# Analog.net
KiCad netlist of a schematic drawn in Altium Designer
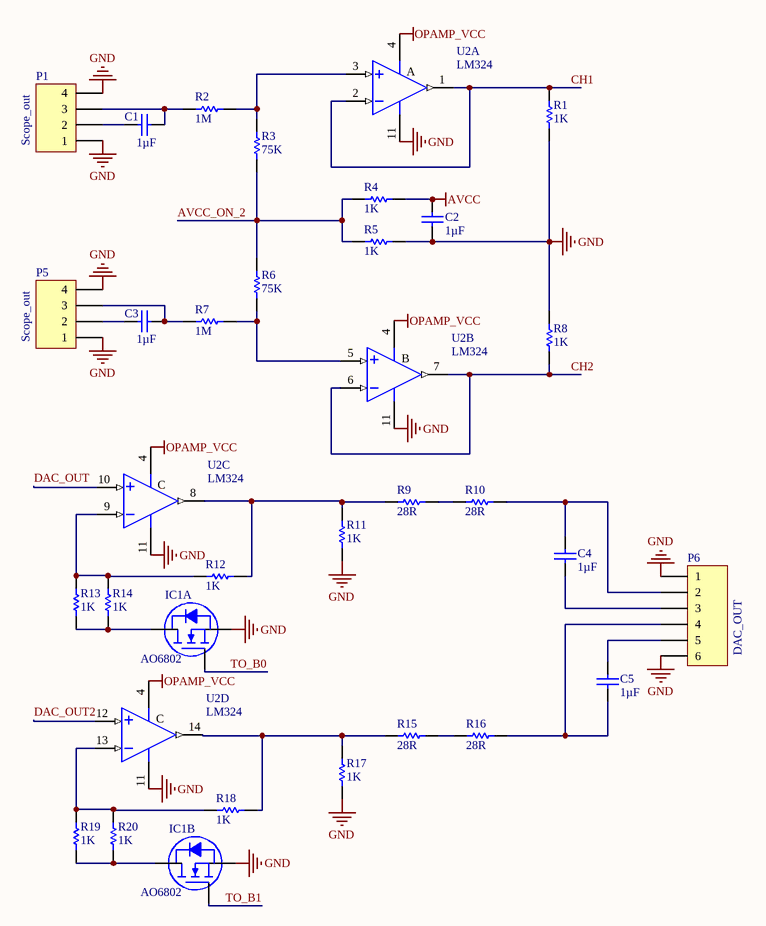
[diagram p0: Analog.SchDoc]

(export (version "E")
  (design (tool "Eeschema 10.0.6"))
  (components
    (comp (ref "C1")
      (value "1µF")
      (footprint "CAPC200X125X75L45N")
      (description "1µF 25V Ceramic Capacitor X5R 0805 (2012 Metric) 0.079\" L x 0.049\" W (2.00mm x 1.25mm)")
      (fields
        (field (name "MANUFACTURER") "Wurth Electronics")
        (field (name "MANUFACTURER PART NUMBER") "885012107015")
      )
      (libsource (lib "labrador") (part "885012107015"))
    )
    (comp (ref "C2")
      (value "1µF")
      (footprint "CAPC200X125X75L45N")
      (description "1µF 25V Ceramic Capacitor X5R 0805 (2012 Metric) 0.079\" L x 0.049\" W (2.00mm x 1.25mm)")
      (fields
        (field (name "MANUFACTURER") "Wurth Electronics")
        (field (name "MANUFACTURER PART NUMBER") "885012107015")
      )
      (libsource (lib "labrador") (part "885012107015"))
    )
    (comp (ref "C3")
      (value "1µF")
      (footprint "CAPC200X125X75L45N")
      (description "1µF 25V Ceramic Capacitor X5R 0805 (2012 Metric) 0.079\" L x 0.049\" W (2.00mm x 1.25mm)")
      (fields
        (field (name "MANUFACTURER") "Wurth Electronics")
        (field (name "MANUFACTURER PART NUMBER") "885012107015")
      )
      (libsource (lib "labrador") (part "885012107015"))
    )
    (comp (ref "C4")
      (value "1µF")
      (footprint "CAPC200X125X75L45N")
      (description "1µF 25V Ceramic Capacitor X5R 0805 (2012 Metric) 0.079\" L x 0.049\" W (2.00mm x 1.25mm)")
      (fields
        (field (name "MANUFACTURER") "Wurth Electronics")
        (field (name "MANUFACTURER PART NUMBER") "885012107015")
      )
      (libsource (lib "labrador") (part "885012107015"))
    )
    (comp (ref "C5")
      (value "1µF")
      (footprint "CAPC200X125X75L45N")
      (description "1µF 25V Ceramic Capacitor X5R 0805 (2012 Metric) 0.079\" L x 0.049\" W (2.00mm x 1.25mm)")
      (fields
        (field (name "MANUFACTURER") "Wurth Electronics")
        (field (name "MANUFACTURER PART NUMBER") "885012107015")
      )
      (libsource (lib "labrador") (part "885012107015"))
    )
    (comp (ref "IC1")
      (value "AO6802")
      (footprint "ALPHAOMEGA TSOP-6")
      (description "MOSFET 2N-CH 30V 3.5A 6-TSOP")
      (fields (field (name "MANUFACTURER") "Alpha & Omega"))
      (libsource (lib "labrador") (part "ALPHAOMEGA TSOP-6"))
    )
    (comp (ref "P1")
      (value "Scope_out")
      (footprint "HDR1X4")
      (description "Header, 4-Pin")
      (fields (field (name "PUBLISHER") "Altium Limited"))
      (libsource (lib "labrador") (part "Header 4"))
    )
    (comp (ref "P5")
      (value "Scope_out")
      (footprint "HDR1X4")
      (description "Header, 4-Pin")
      (fields (field (name "PUBLISHER") "Altium Limited"))
      (libsource (lib "labrador") (part "Header 4"))
    )
    (comp (ref "P6")
      (value "DAC_OUT")
      (footprint "HDR1X6")
      (description "Header, 6-Pin")
      (fields (field (name "PUBLISHER") "Altium Limited"))
      (libsource (lib "labrador") (part "Header 6"))
    )
    (comp (ref "R1")
      (value "1K")
      (footprint "RESC200X125X50L35N")
      (description "RES SMD 1K OHM 1% 1/8W 0805")
      (fields
        (field (name "MANUFACTURER") "Yageo")
        (field (name "MANUFACTURER PART NUMBER") "RC0805FR-071KL")
      )
      (libsource (lib "labrador") (part "RC0805FR-071KL"))
    )
    (comp (ref "R2")
      (value "1M")
      (footprint "RESC200X125X50L35N")
      (description "RES SMD 1M OHM 5% 1/8W 0805")
      (fields
        (field (name "MANUFACTURER") "Yageo")
        (field (name "MANUFACTURER PART NUMBER") "RC0805JR-071ML")
      )
      (libsource (lib "labrador") (part "RC0805JR-071ML"))
    )
    (comp (ref "R3")
      (value "75K")
      (footprint "RESC200X125X50L35N")
      (description "RES SMD 75K OHM 1% 1/8W 0805")
      (fields
        (field (name "MANUFACTURER") "Yageo")
        (field (name "MANUFACTURER PART NUMBER") "RT0805FRE0775KL")
      )
      (libsource (lib "labrador") (part "RT0805FRE0775KL"))
    )
    (comp (ref "R4")
      (value "1K")
      (footprint "RESC200X125X50L35N")
      (description "RES SMD 1K OHM 1% 1/8W 0805")
      (fields
        (field (name "MANUFACTURER") "Yageo")
        (field (name "MANUFACTURER PART NUMBER") "RC0805FR-071KL")
      )
      (libsource (lib "labrador") (part "RC0805FR-071KL"))
    )
    (comp (ref "R5")
      (value "1K")
      (footprint "RESC200X125X50L35N")
      (description "RES SMD 1K OHM 1% 1/8W 0805")
      (fields
        (field (name "MANUFACTURER") "Yageo")
        (field (name "MANUFACTURER PART NUMBER") "RC0805FR-071KL")
      )
      (libsource (lib "labrador") (part "RC0805FR-071KL"))
    )
    (comp (ref "R6")
      (value "75K")
      (footprint "RESC200X125X50L35N")
      (description "RES SMD 75K OHM 1% 1/8W 0805")
      (fields
        (field (name "MANUFACTURER") "Yageo")
        (field (name "MANUFACTURER PART NUMBER") "RT0805FRE0775KL")
      )
      (libsource (lib "labrador") (part "RT0805FRE0775KL"))
    )
    (comp (ref "R7")
      (value "1M")
      (footprint "RESC200X125X50L35N")
      (description "RES SMD 1M OHM 5% 1/8W 0805")
      (fields
        (field (name "MANUFACTURER") "Yageo")
        (field (name "MANUFACTURER PART NUMBER") "RC0805JR-071ML")
      )
      (libsource (lib "labrador") (part "RC0805JR-071ML"))
    )
    (comp (ref "R8")
      (value "1K")
      (footprint "RESC200X125X50L35N")
      (description "RES SMD 1K OHM 1% 1/8W 0805")
      (fields
        (field (name "MANUFACTURER") "Yageo")
        (field (name "MANUFACTURER PART NUMBER") "RC0805FR-071KL")
      )
      (libsource (lib "labrador") (part "RC0805FR-071KL"))
    )
    (comp (ref "R9")
      (value "28R")
      (footprint "RESC160X80X55L25N")
      (description "RES SMD 28 OHM 1% 1/10W 0603")
      (fields
        (field (name "MANUFACTURER") "Yageo")
        (field (name "MANUFACTURER PART NUMBER") "RC0603FR-0728RL")
      )
      (libsource (lib "labrador") (part "RC0603FR-0728RL"))
    )
    (comp (ref "R10")
      (value "28R")
      (footprint "RESC160X80X55L25N")
      (description "RES SMD 28 OHM 1% 1/10W 0603")
      (fields
        (field (name "MANUFACTURER") "Yageo")
        (field (name "MANUFACTURER PART NUMBER") "RC0603FR-0728RL")
      )
      (libsource (lib "labrador") (part "RC0603FR-0728RL"))
    )
    (comp (ref "R11")
      (value "1K")
      (footprint "RESC200X125X50L35N")
      (description "RES SMD 1K OHM 1% 1/8W 0805")
      (fields
        (field (name "MANUFACTURER") "Yageo")
        (field (name "MANUFACTURER PART NUMBER") "RC0805FR-071KL")
      )
      (libsource (lib "labrador") (part "RC0805FR-071KL"))
    )
    (comp (ref "R12")
      (value "1K")
      (footprint "RESC200X125X50L35N")
      (description "RES SMD 1K OHM 1% 1/8W 0805")
      (fields
        (field (name "MANUFACTURER") "Yageo")
        (field (name "MANUFACTURER PART NUMBER") "RC0805FR-071KL")
      )
      (libsource (lib "labrador") (part "RC0805FR-071KL"))
    )
    (comp (ref "R13")
      (value "1K")
      (footprint "RESC200X125X50L35N")
      (description "RES SMD 1K OHM 1% 1/8W 0805")
      (fields
        (field (name "MANUFACTURER") "Yageo")
        (field (name "MANUFACTURER PART NUMBER") "RC0805FR-071KL")
      )
      (libsource (lib "labrador") (part "RC0805FR-071KL"))
    )
    (comp (ref "R14")
      (value "1K")
      (footprint "RESC200X125X50L35N")
      (description "RES SMD 1K OHM 1% 1/8W 0805")
      (fields
        (field (name "MANUFACTURER") "Yageo")
        (field (name "MANUFACTURER PART NUMBER") "RC0805FR-071KL")
      )
      (libsource (lib "labrador") (part "RC0805FR-071KL"))
    )
    (comp (ref "R15")
      (value "28R")
      (footprint "RESC160X80X55L25N")
      (description "RES SMD 28 OHM 1% 1/10W 0603")
      (fields
        (field (name "MANUFACTURER") "Yageo")
        (field (name "MANUFACTURER PART NUMBER") "RC0603FR-0728RL")
      )
      (libsource (lib "labrador") (part "RC0603FR-0728RL"))
    )
    (comp (ref "R16")
      (value "28R")
      (footprint "RESC160X80X55L25N")
      (description "RES SMD 28 OHM 1% 1/10W 0603")
      (fields
        (field (name "MANUFACTURER") "Yageo")
        (field (name "MANUFACTURER PART NUMBER") "RC0603FR-0728RL")
      )
      (libsource (lib "labrador") (part "RC0603FR-0728RL"))
    )
    (comp (ref "R17")
      (value "1K")
      (footprint "RESC200X125X50L35N")
      (description "RES SMD 1K OHM 1% 1/8W 0805")
      (fields
        (field (name "MANUFACTURER") "Yageo")
        (field (name "MANUFACTURER PART NUMBER") "RC0805FR-071KL")
      )
      (libsource (lib "labrador") (part "RC0805FR-071KL"))
    )
    (comp (ref "R18")
      (value "1K")
      (footprint "RESC200X125X50L35N")
      (description "RES SMD 1K OHM 1% 1/8W 0805")
      (fields
        (field (name "MANUFACTURER") "Yageo")
        (field (name "MANUFACTURER PART NUMBER") "RC0805FR-071KL")
      )
      (libsource (lib "labrador") (part "RC0805FR-071KL"))
    )
    (comp (ref "R19")
      (value "1K")
      (footprint "RESC200X125X50L35N")
      (description "RES SMD 1K OHM 1% 1/8W 0805")
      (fields
        (field (name "MANUFACTURER") "Yageo")
        (field (name "MANUFACTURER PART NUMBER") "RC0805FR-071KL")
      )
      (libsource (lib "labrador") (part "RC0805FR-071KL"))
    )
    (comp (ref "R20")
      (value "1K")
      (footprint "RESC200X125X50L35N")
      (description "RES SMD 1K OHM 1% 1/8W 0805")
      (fields
        (field (name "MANUFACTURER") "Yageo")
        (field (name "MANUFACTURER PART NUMBER") "RC0805FR-071KL")
      )
      (libsource (lib "labrador") (part "RC0805FR-071KL"))
    )
    (comp (ref "U2")
      (value "LM324")
      (footprint "SOIC14P127_865X600X175L83X41N")
      (description "IC OPAMP GP 14SOIC")
      (fields
        (field (name "MANUFACTURER") "ON Semiconductor / Fairchild")
        (field (name "MANUFACTURER PART NUMBER") "LM324MX")
      )
      (libsource (lib "labrador") (part "LM324MX"))
    )
  )
  (nets
    (net (code "1") (name "/AVCC_ON_2") (class "Default")
      (node (ref "R3") (pin "1") (pinfunction "1_1") (pintype "passive"))
      (node (ref "R4") (pin "1") (pinfunction "1_1") (pintype "passive"))
      (node (ref "R5") (pin "1") (pinfunction "1_1") (pintype "passive"))
      (node (ref "R6") (pin "2") (pinfunction "2_2") (pintype "passive"))
    )
    (net (code "2") (name "/CH1") (class "Default")
      (node (ref "R1") (pin "2") (pinfunction "2_2") (pintype "passive"))
      (node (ref "U2") (pin "1") (pinfunction "OUTA_1") (pintype "output"))
      (node (ref "U2") (pin "2") (pinfunction "IN-_2") (pintype "input"))
    )
    (net (code "3") (name "/CH2") (class "Default")
      (node (ref "R8") (pin "1") (pinfunction "1_1") (pintype "passive"))
      (node (ref "U2") (pin "6") (pinfunction "IN-_6") (pintype "input"))
      (node (ref "U2") (pin "7") (pinfunction "OUTB_7") (pintype "output"))
    )
    (net (code "4") (name "/DAC_OUT") (class "Default")
      (node (ref "U2") (pin "10") (pinfunction "IN+_10") (pintype "input"))
    )
    (net (code "5") (name "/DAC_OUT2") (class "Default")
      (node (ref "U2") (pin "12") (pinfunction "IN+_12") (pintype "input"))
    )
    (net (code "6") (name "/TO_B0") (class "Default")
      (node (ref "IC1") (pin "1") (pinfunction "G1_1") (pintype "passive"))
    )
    (net (code "7") (name "/TO_B1") (class "Default")
      (node (ref "IC1") (pin "3") (pinfunction "G2_3") (pintype "passive"))
    )
    (net (code "8") (name "AVCC") (class "Default")
      (node (ref "C2") (pin "2") (pinfunction "2_2") (pintype "passive"))
      (node (ref "R4") (pin "2") (pinfunction "2_2") (pintype "passive"))
    )
    (net (code "9") (name "GND") (class "Default")
      (node (ref "C2") (pin "1") (pinfunction "1_1") (pintype "passive"))
      (node (ref "IC1") (pin "2") (pinfunction "S2_2") (pintype "passive"))
      (node (ref "IC1") (pin "5") (pinfunction "S1_5") (pintype "passive"))
      (node (ref "P1") (pin "1") (pinfunction "1_1") (pintype "passive"))
      (node (ref "P1") (pin "4") (pinfunction "4_4") (pintype "passive"))
      (node (ref "P5") (pin "1") (pinfunction "1_1") (pintype "passive"))
      (node (ref "P5") (pin "4") (pinfunction "4_4") (pintype "passive"))
      (node (ref "P6") (pin "1") (pinfunction "1_1") (pintype "passive"))
      (node (ref "P6") (pin "6") (pinfunction "6_6") (pintype "passive"))
      (node (ref "R1") (pin "1") (pinfunction "1_1") (pintype "passive"))
      (node (ref "R11") (pin "1") (pinfunction "1_1") (pintype "passive"))
      (node (ref "R17") (pin "1") (pinfunction "1_1") (pintype "passive"))
      (node (ref "R5") (pin "2") (pinfunction "2_2") (pintype "passive"))
      (node (ref "R8") (pin "2") (pinfunction "2_2") (pintype "passive"))
      (node (ref "U2") (pin "11") (pinfunction "V-_11") (pintype "power_in"))
    )
    (net (code "10") (name "Net-(C1-Pad1)") (class "Default")
      (node (ref "C1") (pin "1") (pinfunction "1_1") (pintype "passive"))
      (node (ref "P1") (pin "2") (pinfunction "2_2") (pintype "passive"))
    )
    (net (code "11") (name "Net-(C1-Pad2)") (class "Default")
      (node (ref "C1") (pin "2") (pinfunction "2_2") (pintype "passive"))
      (node (ref "P1") (pin "3") (pinfunction "3_3") (pintype "passive"))
      (node (ref "R2") (pin "1") (pinfunction "1_1") (pintype "passive"))
    )
    (net (code "12") (name "Net-(C3-Pad1)") (class "Default")
      (node (ref "C3") (pin "1") (pinfunction "1_1") (pintype "passive"))
      (node (ref "P5") (pin "2") (pinfunction "2_2") (pintype "passive"))
    )
    (net (code "13") (name "Net-(C3-Pad2)") (class "Default")
      (node (ref "C3") (pin "2") (pinfunction "2_2") (pintype "passive"))
      (node (ref "P5") (pin "3") (pinfunction "3_3") (pintype "passive"))
      (node (ref "R7") (pin "1") (pinfunction "1_1") (pintype "passive"))
    )
    (net (code "14") (name "Net-(C4-Pad1)") (class "Default")
      (node (ref "C4") (pin "1") (pinfunction "1_1") (pintype "passive"))
      (node (ref "P6") (pin "3") (pinfunction "3_3") (pintype "passive"))
    )
    (net (code "15") (name "Net-(C4-Pad2)") (class "Default")
      (node (ref "C4") (pin "2") (pinfunction "2_2") (pintype "passive"))
      (node (ref "P6") (pin "2") (pinfunction "2_2") (pintype "passive"))
      (node (ref "R10") (pin "2") (pinfunction "2_2") (pintype "passive"))
    )
    (net (code "16") (name "Net-(C5-Pad1)") (class "Default")
      (node (ref "C5") (pin "1") (pinfunction "1_1") (pintype "passive"))
      (node (ref "P6") (pin "4") (pinfunction "4_4") (pintype "passive"))
      (node (ref "R16") (pin "2") (pinfunction "2_2") (pintype "passive"))
    )
    (net (code "17") (name "Net-(C5-Pad2)") (class "Default")
      (node (ref "C5") (pin "2") (pinfunction "2_2") (pintype "passive"))
      (node (ref "P6") (pin "5") (pinfunction "5_5") (pintype "passive"))
    )
    (net (code "18") (name "Net-(IC1A-D1)") (class "Default")
      (node (ref "IC1") (pin "6") (pinfunction "D1_6") (pintype "passive"))
      (node (ref "R13") (pin "1") (pinfunction "1_1") (pintype "passive"))
      (node (ref "R14") (pin "1") (pinfunction "1_1") (pintype "passive"))
    )
    (net (code "19") (name "Net-(IC1B-D2)") (class "Default")
      (node (ref "IC1") (pin "4") (pinfunction "D2_4") (pintype "passive"))
      (node (ref "R19") (pin "2") (pinfunction "2_2") (pintype "passive"))
      (node (ref "R20") (pin "2") (pinfunction "2_2") (pintype "passive"))
    )
    (net (code "20") (name "Net-(R10-Pad1)") (class "Default")
      (node (ref "R10") (pin "1") (pinfunction "1_1") (pintype "passive"))
      (node (ref "R9") (pin "2") (pinfunction "2_2") (pintype "passive"))
    )
    (net (code "21") (name "Net-(R15-Pad2)") (class "Default")
      (node (ref "R15") (pin "2") (pinfunction "2_2") (pintype "passive"))
      (node (ref "R16") (pin "1") (pinfunction "1_1") (pintype "passive"))
    )
    (net (code "22") (name "Net-(U2A-IN+)") (class "Default")
      (node (ref "R2") (pin "2") (pinfunction "2_2") (pintype "passive"))
      (node (ref "R3") (pin "2") (pinfunction "2_2") (pintype "passive"))
      (node (ref "U2") (pin "3") (pinfunction "IN+_3") (pintype "input"))
    )
    (net (code "23") (name "Net-(U2B-IN+)") (class "Default")
      (node (ref "R6") (pin "1") (pinfunction "1_1") (pintype "passive"))
      (node (ref "R7") (pin "2") (pinfunction "2_2") (pintype "passive"))
      (node (ref "U2") (pin "5") (pinfunction "IN+_5") (pintype "input"))
    )
    (net (code "24") (name "Net-(U2C-IN-)") (class "Default")
      (node (ref "R12") (pin "2") (pinfunction "2_2") (pintype "passive"))
      (node (ref "R13") (pin "2") (pinfunction "2_2") (pintype "passive"))
      (node (ref "R14") (pin "2") (pinfunction "2_2") (pintype "passive"))
      (node (ref "U2") (pin "9") (pinfunction "IN-_9") (pintype "input"))
    )
    (net (code "25") (name "Net-(U2C-OUTC)") (class "Default")
      (node (ref "R11") (pin "2") (pinfunction "2_2") (pintype "passive"))
      (node (ref "R12") (pin "1") (pinfunction "1_1") (pintype "passive"))
      (node (ref "R9") (pin "1") (pinfunction "1_1") (pintype "passive"))
      (node (ref "U2") (pin "8") (pinfunction "OUTC_8") (pintype "output"))
    )
    (net (code "26") (name "Net-(U2D-IN-)") (class "Default")
      (node (ref "R18") (pin "1") (pinfunction "1_1") (pintype "passive"))
      (node (ref "R19") (pin "1") (pinfunction "1_1") (pintype "passive"))
      (node (ref "R20") (pin "1") (pinfunction "1_1") (pintype "passive"))
      (node (ref "U2") (pin "13") (pinfunction "IN-_13") (pintype "input"))
    )
    (net (code "27") (name "Net-(U2D-OUTD)") (class "Default")
      (node (ref "R15") (pin "1") (pinfunction "1_1") (pintype "passive"))
      (node (ref "R17") (pin "2") (pinfunction "2_2") (pintype "passive"))
      (node (ref "R18") (pin "2") (pinfunction "2_2") (pintype "passive"))
      (node (ref "U2") (pin "14") (pinfunction "OUTD_14") (pintype "output"))
    )
    (net (code "28") (name "OPAMP_VCC") (class "Default")
      (node (ref "U2") (pin "4") (pinfunction "V+_4") (pintype "power_in"))
    )
  )
)
